# Power_Supply.net
KiCad netlist of a schematic drawn in Altium Designer
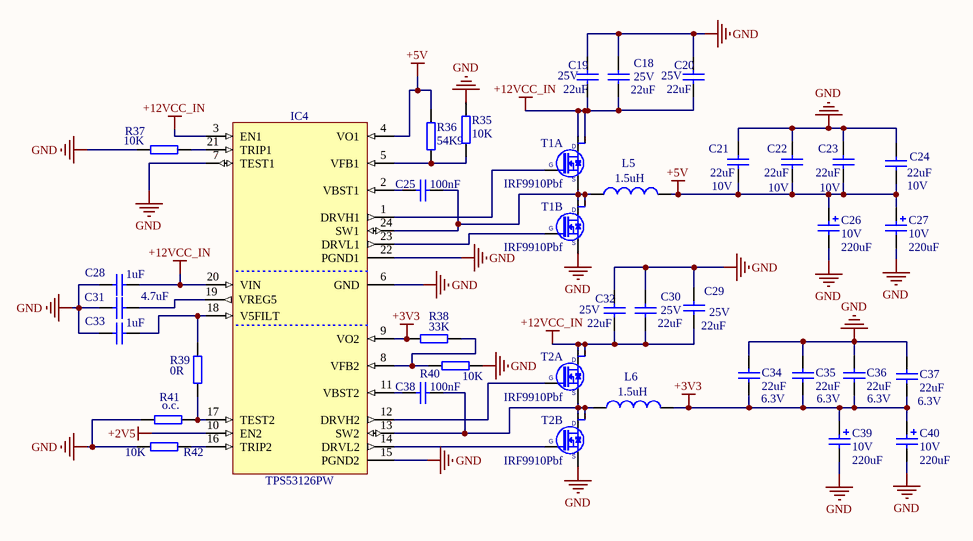
[diagram p0: Power_Supply.SchDoc]

(export (version "E")
  (design (tool "Eeschema 10.0.6"))
  (components
    (comp (ref "C18")
      (value "22uF")
      (footprint "CC3216-1206")
      (description "Capacitor")
      (fields
        (field (name "TOLERANCE") "±10%")
        (field (name "VOLTAGE") "25V")
        (field (name "Comment") "22uF 25V")
        (field (name "PUBLISHER") "Altium Limited")
      )
      (libsource (lib "wr_switch") (part "Cap"))
    )
    (comp (ref "C19")
      (value "22uF")
      (footprint "CC3216-1206")
      (description "Capacitor")
      (fields
        (field (name "TOLERANCE") "±10%")
        (field (name "VOLTAGE") "25V")
        (field (name "Comment") "22uF 25V")
        (field (name "PUBLISHER") "Altium Limited")
      )
      (libsource (lib "wr_switch") (part "Cap"))
    )
    (comp (ref "C20")
      (value "22uF")
      (footprint "CC3216-1206")
      (description "Capacitor")
      (fields
        (field (name "TOLERANCE") "±10%")
        (field (name "VOLTAGE") "25V")
        (field (name "Comment") "22uF 25V")
        (field (name "PUBLISHER") "Altium Limited")
      )
      (libsource (lib "wr_switch") (part "Cap"))
    )
    (comp (ref "C21")
      (value "22uF")
      (footprint "CC2012-0805")
      (description "Capacitor")
      (fields
        (field (name "TOLERANCE") "±10%")
        (field (name "VOLTAGE") "10V")
        (field (name "Comment") "22uF 10V")
        (field (name "PUBLISHER") "Altium Limited")
      )
      (libsource (lib "wr_switch") (part "Cap"))
    )
    (comp (ref "C22")
      (value "22uF")
      (footprint "CC2012-0805")
      (description "Capacitor")
      (fields
        (field (name "TOLERANCE") "±10%")
        (field (name "VOLTAGE") "10V")
        (field (name "Comment") "22uF 10V")
        (field (name "PUBLISHER") "Altium Limited")
      )
      (libsource (lib "wr_switch") (part "Cap"))
    )
    (comp (ref "C23")
      (value "22uF")
      (footprint "CC2012-0805")
      (description "Capacitor")
      (fields
        (field (name "TOLERANCE") "±10%")
        (field (name "VOLTAGE") "10V")
        (field (name "Comment") "22uF 10V")
        (field (name "PUBLISHER") "Altium Limited")
      )
      (libsource (lib "wr_switch") (part "Cap"))
    )
    (comp (ref "C24")
      (value "22uF")
      (footprint "CC2012-0805")
      (description "Capacitor")
      (fields
        (field (name "TOLERANCE") "±10%")
        (field (name "VOLTAGE") "10V")
        (field (name "Comment") "22uF 10V")
        (field (name "PUBLISHER") "Altium Limited")
      )
      (libsource (lib "wr_switch") (part "Cap"))
    )
    (comp (ref "C25")
      (value "100nF")
      (footprint "CC1608-0603")
      (description "Capacitor")
      (fields
        (field (name "TOLERANCE") "±10%")
        (field (name "VOLTAGE") "16V")
        (field (name "PUBLISHER") "Altium Limited")
      )
      (libsource (lib "wr_switch") (part "Cap"))
    )
    (comp (ref "C26")
      (value "220uF")
      (footprint "D")
      (description "Polarized Capacitor Tantalum")
      (fields
        (field (name "TOLERANCE") "±20%")
        (field (name "VOLTAGE") "10V")
        (field (name "Comment") "220uF 10V")
        (field (name "PUBLISHER") "Altium Limited")
      )
      (libsource (lib "wr_switch") (part "Cap Pol1"))
    )
    (comp (ref "C27")
      (value "220uF")
      (footprint "D")
      (description "Polarized Capacitor Tantalum")
      (fields
        (field (name "TOLERANCE") "±20%")
        (field (name "VOLTAGE") "10V")
        (field (name "Comment") "220uF 10V")
        (field (name "PUBLISHER") "Altium Limited")
      )
      (libsource (lib "wr_switch") (part "Cap Pol1"))
    )
    (comp (ref "C28")
      (value "1uF")
      (footprint "CC1608-0603")
      (description "Capacitor")
      (fields
        (field (name "TOLERANCE") "±10%")
        (field (name "VOLTAGE") "25V")
        (field (name "PUBLISHER") "Altium Limited")
      )
      (libsource (lib "wr_switch") (part "Cap"))
    )
    (comp (ref "C29")
      (value "22uF")
      (footprint "CC3216-1206")
      (description "Capacitor")
      (fields
        (field (name "TOLERANCE") "±10%")
        (field (name "VOLTAGE") "25V")
        (field (name "Comment") "22uF 25V")
        (field (name "PUBLISHER") "Altium Limited")
      )
      (libsource (lib "wr_switch") (part "Cap"))
    )
    (comp (ref "C30")
      (value "22uF")
      (footprint "CC3216-1206")
      (description "Capacitor")
      (fields
        (field (name "TOLERANCE") "±10%")
        (field (name "VOLTAGE") "25V")
        (field (name "Comment") "22uF 25V")
        (field (name "PUBLISHER") "Altium Limited")
      )
      (libsource (lib "wr_switch") (part "Cap"))
    )
    (comp (ref "C31")
      (value "4.7uF")
      (footprint "CC1608-0603")
      (description "Capacitor")
      (fields
        (field (name "TOLERANCE") "±10%")
        (field (name "VOLTAGE") "10V")
        (field (name "PUBLISHER") "Altium Limited")
      )
      (libsource (lib "wr_switch") (part "Cap"))
    )
    (comp (ref "C32")
      (value "22uF")
      (footprint "CC3216-1206")
      (description "Capacitor")
      (fields
        (field (name "TOLERANCE") "±10%")
        (field (name "VOLTAGE") "25V")
        (field (name "Comment") "22uF 25V")
        (field (name "PUBLISHER") "Altium Limited")
      )
      (libsource (lib "wr_switch") (part "Cap"))
    )
    (comp (ref "C33")
      (value "1uF")
      (footprint "CC1608-0603")
      (description "Capacitor")
      (fields
        (field (name "TOLERANCE") "±10%")
        (field (name "VOLTAGE") "25V")
        (field (name "PUBLISHER") "Altium Limited")
      )
      (libsource (lib "wr_switch") (part "Cap"))
    )
    (comp (ref "C34")
      (value "22uF")
      (footprint "CC2012-0805")
      (description "Capacitor")
      (fields
        (field (name "TOLERANCE") "±20%")
        (field (name "VOLTAGE") "6.3V")
        (field (name "PUBLISHER") "Altium Limited")
      )
      (libsource (lib "wr_switch") (part "Cap"))
    )
    (comp (ref "C35")
      (value "22uF")
      (footprint "CC2012-0805")
      (description "Capacitor")
      (fields
        (field (name "TOLERANCE") "±20%")
        (field (name "VOLTAGE") "6.3V")
        (field (name "PUBLISHER") "Altium Limited")
      )
      (libsource (lib "wr_switch") (part "Cap"))
    )
    (comp (ref "C36")
      (value "22uF")
      (footprint "CC2012-0805")
      (description "Capacitor")
      (fields
        (field (name "TOLERANCE") "±20%")
        (field (name "VOLTAGE") "6.3V")
        (field (name "PUBLISHER") "Altium Limited")
      )
      (libsource (lib "wr_switch") (part "Cap"))
    )
    (comp (ref "C37")
      (value "22uF")
      (footprint "CC2012-0805")
      (description "Capacitor")
      (fields
        (field (name "TOLERANCE") "±20%")
        (field (name "VOLTAGE") "6.3V")
        (field (name "PUBLISHER") "Altium Limited")
      )
      (libsource (lib "wr_switch") (part "Cap"))
    )
    (comp (ref "C38")
      (value "100nF")
      (footprint "CC1608-0603")
      (description "Capacitor")
      (fields
        (field (name "TOLERANCE") "±10%")
        (field (name "VOLTAGE") "16V")
        (field (name "PUBLISHER") "Altium Limited")
      )
      (libsource (lib "wr_switch") (part "Cap"))
    )
    (comp (ref "C39")
      (value "220uF")
      (footprint "D")
      (description "Polarized Capacitor Tantalum")
      (fields
        (field (name "TOLERANCE") "±20%")
        (field (name "VOLTAGE") "10V")
        (field (name "Comment") "220uF 10V")
        (field (name "PUBLISHER") "Altium Limited")
      )
      (libsource (lib "wr_switch") (part "Cap Pol1"))
    )
    (comp (ref "C40")
      (value "220uF")
      (footprint "D")
      (description "Polarized Capacitor Tantalum")
      (fields
        (field (name "TOLERANCE") "±20%")
        (field (name "VOLTAGE") "10V")
        (field (name "Comment") "220uF 10V")
        (field (name "PUBLISHER") "Altium Limited")
      )
      (libsource (lib "wr_switch") (part "Cap Pol1"))
    )
    (comp (ref "IC4")
      (value "TPS53126PW")
      (footprint "SOP65P640X120-24N")
      (description "Dual Synchronous Step-Down Controller For Low Voltage Power Rails")
      (fields (field (name "AUTHOR") "CERN DEM JLC"))
      (libsource (lib "wr_switch") (part "TPS53126PW"))
    )
    (comp (ref "L5")
      (value "1.5uH")
      (footprint "IHLP2525")
      (description "Low Profile, High Current Inductor")
      (fields
        (field (name "MANUFACTURER") "Vishay/Dale")
        (field (name "Comment") "IHLP2525CZER1R5M01")
        (field (name "PUBLISHER") "Altium Limited")
      )
      (libsource (lib "Miscellaneous Devices") (part "Inductor"))
    )
    (comp (ref "L6")
      (value "1.5uH")
      (footprint "IHLP2525")
      (description "Low Profile, High Current Inductor")
      (fields
        (field (name "MANUFACTURER") "Vishay/Dale")
        (field (name "Comment") "IHLP2525CZER1R5M01")
        (field (name "PUBLISHER") "Altium Limited")
      )
      (libsource (lib "Miscellaneous Devices") (part "Inductor"))
    )
    (comp (ref "R35")
      (value "10K")
      (footprint "0603")
      (description "SMD Resistor")
      (fields (field (name "TOLERANCE") "±1%"))
      (libsource (lib "wr_switch") (part "RES_SMD"))
    )
    (comp (ref "R36")
      (value "54K9")
      (footprint "0603")
      (description "SMD Resistor")
      (fields (field (name "TOLERANCE") "±1%"))
      (libsource (lib "wr_switch") (part "RES_SMD"))
    )
    (comp (ref "R37")
      (value "10K")
      (footprint "0603")
      (description "SMD Resistor")
      (fields (field (name "TOLERANCE") "±1%"))
      (libsource (lib "wr_switch") (part "RES_SMD"))
    )
    (comp (ref "R38")
      (value "33K")
      (footprint "0603")
      (description "SMD Resistor")
      (fields (field (name "TOLERANCE") "±1%"))
      (libsource (lib "wr_switch") (part "RES_SMD"))
    )
    (comp (ref "R39")
      (value "0R")
      (footprint "0603")
      (description "SMD Resistor")
      (libsource (lib "wr_switch") (part "RES_SMD"))
    )
    (comp (ref "R40")
      (value "10K")
      (footprint "0603")
      (description "SMD Resistor")
      (fields (field (name "TOLERANCE") "±1%"))
      (libsource (lib "wr_switch") (part "RES_SMD"))
    )
    (comp (ref "R41")
      (value "o.c.")
      (footprint "0603")
      (description "SMD Resistor")
      (fields (field (name "TOLERANCE") "NA"))
      (libsource (lib "wr_switch") (part "RES_SMD"))
    )
    (comp (ref "R42")
      (value "10K")
      (footprint "0603")
      (description "SMD Resistor")
      (fields (field (name "TOLERANCE") "±1%"))
      (libsource (lib "wr_switch") (part "RES_SMD"))
    )
    (comp (ref "T1")
      (value "IRF9910Pbf")
      (footprint "SOIC127P600X175-8N")
      (description "Dual SO-8 MOSFET For POL Cconverter")
      (fields (field (name "MANUFACTURER") "INTERNATIONAL RECTIFIER") (field (name "AUTHOR") "CERN DEM JLC"))
      (libsource (lib "ICs And Semiconductors") (part "IRF9910"))
    )
    (comp (ref "T2")
      (value "IRF9910Pbf")
      (footprint "SOIC127P600X175-8N")
      (description "Dual SO-8 MOSFET For POL Cconverter")
      (fields (field (name "MANUFACTURER") "INTERNATIONAL RECTIFIER") (field (name "AUTHOR") "CERN DEM JLC"))
      (libsource (lib "ICs And Semiconductors") (part "IRF9910"))
    )
  )
  (nets
    (net (code "1") (name "+2V5") (class "Default")
      (node (ref "IC4") (pin "10") (pinfunction "EN2_10") (pintype "input"))
    )
    (net (code "2") (name "+3V3") (class "Default")
      (node (ref "C34") (pin "2") (pinfunction "2_2") (pintype "passive"))
      (node (ref "C35") (pin "1") (pinfunction "1_1") (pintype "passive"))
      (node (ref "C36") (pin "1") (pinfunction "1_1") (pintype "passive"))
      (node (ref "C37") (pin "1") (pinfunction "1_1") (pintype "passive"))
      (node (ref "C39") (pin "1") (pinfunction "1_1") (pintype "passive"))
      (node (ref "C40") (pin "1") (pinfunction "1_1") (pintype "passive"))
      (node (ref "IC4") (pin "9") (pinfunction "VO2_9") (pintype "input"))
      (node (ref "L6") (pin "2") (pinfunction "2_2") (pintype "passive"))
      (node (ref "R38") (pin "1") (pinfunction "1_1") (pintype "passive"))
    )
    (net (code "3") (name "+5V") (class "Default")
      (node (ref "C21") (pin "1") (pinfunction "1_1") (pintype "passive"))
      (node (ref "C22") (pin "1") (pinfunction "1_1") (pintype "passive"))
      (node (ref "C23") (pin "1") (pinfunction "1_1") (pintype "passive"))
      (node (ref "C24") (pin "1") (pinfunction "1_1") (pintype "passive"))
      (node (ref "C26") (pin "1") (pinfunction "1_1") (pintype "passive"))
      (node (ref "C27") (pin "1") (pinfunction "1_1") (pintype "passive"))
      (node (ref "IC4") (pin "4") (pinfunction "VO1_4") (pintype "input"))
      (node (ref "L5") (pin "2") (pinfunction "2_2") (pintype "passive"))
      (node (ref "R36") (pin "2") (pinfunction "2_2") (pintype "passive"))
    )
    (net (code "4") (name "+12VCC_IN") (class "Default")
      (node (ref "C18") (pin "1") (pinfunction "1_1") (pintype "passive"))
      (node (ref "C19") (pin "1") (pinfunction "1_1") (pintype "passive"))
      (node (ref "C20") (pin "1") (pinfunction "1_1") (pintype "passive"))
      (node (ref "C28") (pin "2") (pinfunction "2_2") (pintype "passive"))
      (node (ref "C29") (pin "1") (pinfunction "1_1") (pintype "passive"))
      (node (ref "C30") (pin "1") (pinfunction "1_1") (pintype "passive"))
      (node (ref "C32") (pin "1") (pinfunction "1_1") (pintype "passive"))
      (node (ref "IC4") (pin "20") (pinfunction "VIN_20") (pintype "input"))
      (node (ref "IC4") (pin "3") (pinfunction "EN1_3") (pintype "input"))
      (node (ref "T1") (pin "5") (pinfunction "D_5") (pintype "passive"))
      (node (ref "T1") (pin "6") (pinfunction "D_6") (pintype "passive"))
      (node (ref "T2") (pin "5") (pinfunction "D_5") (pintype "passive"))
      (node (ref "T2") (pin "6") (pinfunction "D_6") (pintype "passive"))
    )
    (net (code "5") (name "GND") (class "Default")
      (node (ref "C18") (pin "2") (pinfunction "2_2") (pintype "passive"))
      (node (ref "C19") (pin "2") (pinfunction "2_2") (pintype "passive"))
      (node (ref "C20") (pin "2") (pinfunction "2_2") (pintype "passive"))
      (node (ref "C21") (pin "2") (pinfunction "2_2") (pintype "passive"))
      (node (ref "C22") (pin "2") (pinfunction "2_2") (pintype "passive"))
      (node (ref "C23") (pin "2") (pinfunction "2_2") (pintype "passive"))
      (node (ref "C24") (pin "2") (pinfunction "2_2") (pintype "passive"))
      (node (ref "C26") (pin "2") (pinfunction "2_2") (pintype "passive"))
      (node (ref "C27") (pin "2") (pinfunction "2_2") (pintype "passive"))
      (node (ref "C28") (pin "1") (pinfunction "1_1") (pintype "passive"))
      (node (ref "C29") (pin "2") (pinfunction "2_2") (pintype "passive"))
      (node (ref "C30") (pin "2") (pinfunction "2_2") (pintype "passive"))
      (node (ref "C31") (pin "2") (pinfunction "2_2") (pintype "passive"))
      (node (ref "C32") (pin "2") (pinfunction "2_2") (pintype "passive"))
      (node (ref "C33") (pin "1") (pinfunction "1_1") (pintype "passive"))
      (node (ref "C34") (pin "1") (pinfunction "1_1") (pintype "passive"))
      (node (ref "C35") (pin "2") (pinfunction "2_2") (pintype "passive"))
      (node (ref "C36") (pin "2") (pinfunction "2_2") (pintype "passive"))
      (node (ref "C37") (pin "2") (pinfunction "2_2") (pintype "passive"))
      (node (ref "C39") (pin "2") (pinfunction "2_2") (pintype "passive"))
      (node (ref "C40") (pin "2") (pinfunction "2_2") (pintype "passive"))
      (node (ref "IC4") (pin "15") (pinfunction "PGND2_15") (pintype "power_in"))
      (node (ref "IC4") (pin "22") (pinfunction "PGND1_22") (pintype "power_in"))
      (node (ref "IC4") (pin "6") (pinfunction "GND_6") (pintype "power_in"))
      (node (ref "IC4") (pin "7") (pinfunction "TEST1_7") (pintype "bidirectional"))
      (node (ref "R35") (pin "2") (pinfunction "2_2") (pintype "passive"))
      (node (ref "R37") (pin "2") (pinfunction "2_2") (pintype "passive"))
      (node (ref "R40") (pin "1") (pinfunction "1_1") (pintype "passive"))
      (node (ref "R41") (pin "2") (pinfunction "2_2") (pintype "passive"))
      (node (ref "R42") (pin "2") (pinfunction "2_2") (pintype "passive"))
      (node (ref "T1") (pin "1") (pinfunction "S_1") (pintype "passive"))
      (node (ref "T2") (pin "1") (pinfunction "S_1") (pintype "passive"))
    )
    (net (code "6") (name "Net-(IC4-DRVH1)") (class "Default")
      (node (ref "IC4") (pin "1") (pinfunction "DRVH1_1") (pintype "output"))
      (node (ref "T1") (pin "4") (pinfunction "G_4") (pintype "passive"))
    )
    (net (code "7") (name "Net-(IC4-DRVH2)") (class "Default")
      (node (ref "IC4") (pin "12") (pinfunction "DRVH2_12") (pintype "output"))
      (node (ref "T2") (pin "4") (pinfunction "G_4") (pintype "passive"))
    )
    (net (code "8") (name "Net-(IC4-DRVL1)") (class "Default")
      (node (ref "IC4") (pin "23") (pinfunction "DRVL1_23") (pintype "output"))
      (node (ref "T1") (pin "2") (pinfunction "G_2") (pintype "passive"))
    )
    (net (code "9") (name "Net-(IC4-DRVL2)") (class "Default")
      (node (ref "IC4") (pin "14") (pinfunction "DRVL2_14") (pintype "output"))
      (node (ref "T2") (pin "2") (pinfunction "G_2") (pintype "passive"))
    )
    (net (code "10") (name "Net-(IC4-SW1)") (class "Default")
      (node (ref "C25") (pin "1") (pinfunction "1_1") (pintype "passive"))
      (node (ref "IC4") (pin "24") (pinfunction "SW1_24") (pintype "bidirectional"))
      (node (ref "L5") (pin "1") (pinfunction "1_1") (pintype "passive"))
      (node (ref "T1") (pin "3") (pinfunction "S_3") (pintype "passive"))
      (node (ref "T1") (pin "7") (pinfunction "D_7") (pintype "passive"))
      (node (ref "T1") (pin "8") (pinfunction "D_8") (pintype "passive"))
    )
    (net (code "11") (name "Net-(IC4-SW2)") (class "Default")
      (node (ref "C38") (pin "1") (pinfunction "1_1") (pintype "passive"))
      (node (ref "IC4") (pin "13") (pinfunction "SW2_13") (pintype "bidirectional"))
      (node (ref "L6") (pin "1") (pinfunction "1_1") (pintype "passive"))
      (node (ref "T2") (pin "3") (pinfunction "S_3") (pintype "passive"))
      (node (ref "T2") (pin "7") (pinfunction "D_7") (pintype "passive"))
      (node (ref "T2") (pin "8") (pinfunction "D_8") (pintype "passive"))
    )
    (net (code "12") (name "Net-(IC4-TEST2)") (class "Default")
      (node (ref "IC4") (pin "17") (pinfunction "TEST2_17") (pintype "input"))
      (node (ref "R39") (pin "2") (pinfunction "2_2") (pintype "passive"))
      (node (ref "R41") (pin "1") (pinfunction "1_1") (pintype "passive"))
    )
    (net (code "13") (name "Net-(IC4-TRIP1)") (class "Default")
      (node (ref "IC4") (pin "21") (pinfunction "TRIP1_21") (pintype "input"))
      (node (ref "R37") (pin "1") (pinfunction "1_1") (pintype "passive"))
    )
    (net (code "14") (name "Net-(IC4-TRIP2)") (class "Default")
      (node (ref "IC4") (pin "16") (pinfunction "TRIP2_16") (pintype "input"))
      (node (ref "R42") (pin "1") (pinfunction "1_1") (pintype "passive"))
    )
    (net (code "15") (name "Net-(IC4-V5FILT)") (class "Default")
      (node (ref "C33") (pin "2") (pinfunction "2_2") (pintype "passive"))
      (node (ref "IC4") (pin "18") (pinfunction "V5FILT_18") (pintype "input"))
      (node (ref "R39") (pin "1") (pinfunction "1_1") (pintype "passive"))
    )
    (net (code "16") (name "Net-(IC4-VBST1)") (class "Default")
      (node (ref "C25") (pin "2") (pinfunction "2_2") (pintype "passive"))
      (node (ref "IC4") (pin "2") (pinfunction "VBST1_2") (pintype "input"))
    )
    (net (code "17") (name "Net-(IC4-VBST2)") (class "Default")
      (node (ref "C38") (pin "2") (pinfunction "2_2") (pintype "passive"))
      (node (ref "IC4") (pin "11") (pinfunction "VBST2_11") (pintype "input"))
    )
    (net (code "18") (name "Net-(IC4-VFB1)") (class "Default")
      (node (ref "IC4") (pin "5") (pinfunction "VFB1_5") (pintype "input"))
      (node (ref "R35") (pin "1") (pinfunction "1_1") (pintype "passive"))
      (node (ref "R36") (pin "1") (pinfunction "1_1") (pintype "passive"))
    )
    (net (code "19") (name "Net-(IC4-VFB2)") (class "Default")
      (node (ref "IC4") (pin "8") (pinfunction "VFB2_8") (pintype "input"))
      (node (ref "R38") (pin "2") (pinfunction "2_2") (pintype "passive"))
      (node (ref "R40") (pin "2") (pinfunction "2_2") (pintype "passive"))
    )
    (net (code "20") (name "Net-(IC4-VREG5)") (class "Default")
      (node (ref "C31") (pin "1") (pinfunction "1_1") (pintype "passive"))
      (node (ref "IC4") (pin "19") (pinfunction "VREG5_19") (pintype "output"))
    )
  )
)
